# Usb_breakout.net
KiCad netlist of a schematic drawn in EAGLE
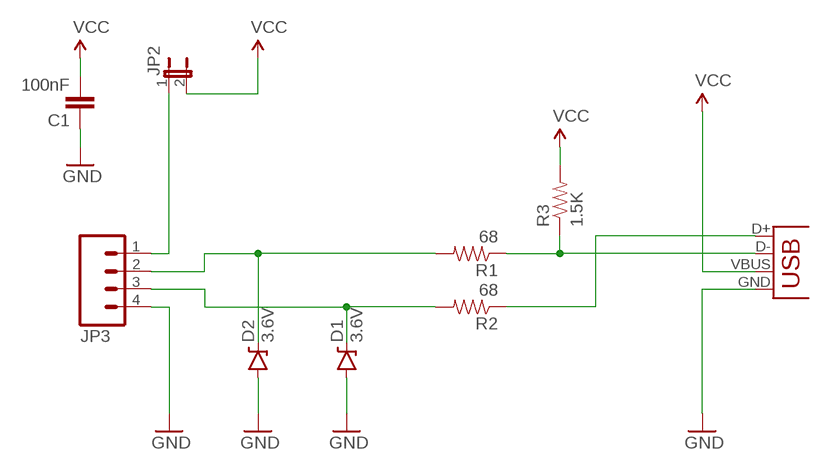
[diagram p0: schematic, sheet 1]

(export (version "E")
  (design (tool "Eeschema 10.0.6"))
  (components
    (comp (ref "C1")
      (value "100nF")
      (footprint "eagle-import:CAP-PTH-SMALLEZ")
      (libsource (lib "eagle-import") (part "CAPEZ"))
    )
    (comp (ref "D1")
      (value "3.6V")
      (footprint "eagle-import:DIODE-ZENER")
      (libsource (lib "eagle-import") (part "DIODE-ZENERPTH"))
    )
    (comp (ref "D2")
      (value "3.6V")
      (footprint "eagle-import:DIODE-ZENER")
      (libsource (lib "eagle-import") (part "DIODE-ZENERPTH"))
    )
    (comp (ref "JP1")
      (value "USB-B")
      (footprint "eagle-import:USB-B-PTH")
      (libsource (lib "eagle-import") (part "USBPTH"))
    )
    (comp (ref "JP2")
      (value "JUMPER-2-OLDPTH")
      (footprint "eagle-import:1X02")
      (libsource (lib "eagle-import") (part "JUMPER-2-OLDPTH"))
    )
    (comp (ref "JP3")
      (value "M04PTH")
      (footprint "eagle-import:1X04")
      (libsource (lib "eagle-import") (part "M04PTH"))
    )
    (comp (ref "R1")
      (value "68")
      (footprint "eagle-import:AXIAL-0.4")
      (libsource (lib "eagle-import") (part "RESISTORPTH-1/4W"))
    )
    (comp (ref "R2")
      (value "68")
      (footprint "eagle-import:AXIAL-0.4")
      (libsource (lib "eagle-import") (part "RESISTORPTH-1/4W"))
    )
    (comp (ref "R3")
      (value "1.5K")
      (footprint "eagle-import:AXIAL-0.4")
      (libsource (lib "eagle-import") (part "RESISTORPTH-1/4W"))
    )
  )
  (nets
    (net (code "1") (name "GND") (class "Default")
      (node (ref "C1") (pin "1") (pinfunction "1_1") (pintype "passive"))
      (node (ref "D1") (pin "P$2") (pinfunction "A_P$2") (pintype "passive"))
      (node (ref "D2") (pin "P$2") (pinfunction "A_P$2") (pintype "passive"))
      (node (ref "JP1") (pin "GND") (pinfunction "GND_GND") (pintype "bidirectional"))
      (node (ref "JP3") (pin "4") (pinfunction "4_4") (pintype "passive"))
    )
    (net (code "2") (name "Net-(D1-C)") (class "Default")
      (node (ref "D1") (pin "P$1") (pinfunction "C_P$1") (pintype "passive"))
      (node (ref "JP3") (pin "3") (pinfunction "3_3") (pintype "passive"))
      (node (ref "R2") (pin "P$2") (pinfunction "2_P$2") (pintype "passive"))
    )
    (net (code "3") (name "Net-(D2-C)") (class "Default")
      (node (ref "D2") (pin "P$1") (pinfunction "C_P$1") (pintype "passive"))
      (node (ref "JP3") (pin "2") (pinfunction "2_2") (pintype "passive"))
      (node (ref "R1") (pin "P$2") (pinfunction "2_P$2") (pintype "passive"))
    )
    (net (code "4") (name "Net-(JP2-Pad1)") (class "Default")
      (node (ref "JP2") (pin "1") (pinfunction "1_1") (pintype "passive"))
      (node (ref "JP3") (pin "1") (pinfunction "1_1") (pintype "passive"))
    )
    (net (code "5") (name "Net-(R1-1)") (class "Default")
      (node (ref "JP1") (pin "D-") (pinfunction "D-_D-") (pintype "bidirectional"))
      (node (ref "R1") (pin "P$1") (pinfunction "1_P$1") (pintype "passive"))
      (node (ref "R3") (pin "P$1") (pinfunction "1_P$1") (pintype "passive"))
    )
    (net (code "6") (name "Net-(R2-1)") (class "Default")
      (node (ref "JP1") (pin "D+") (pinfunction "D+_D+") (pintype "bidirectional"))
      (node (ref "R2") (pin "P$1") (pinfunction "1_P$1") (pintype "passive"))
    )
    (net (code "7") (name "VCC") (class "Default")
      (node (ref "C1") (pin "2") (pinfunction "2_2") (pintype "passive"))
      (node (ref "JP1") (pin "VBUS") (pinfunction "VBUS_VBUS") (pintype "bidirectional"))
      (node (ref "JP2") (pin "2") (pinfunction "2_2") (pintype "passive"))
      (node (ref "R3") (pin "P$2") (pinfunction "2_P$2") (pintype "passive"))
    )
  )
)
